# 477ProjectBattery.net
KiCad netlist of a schematic drawn in EAGLE
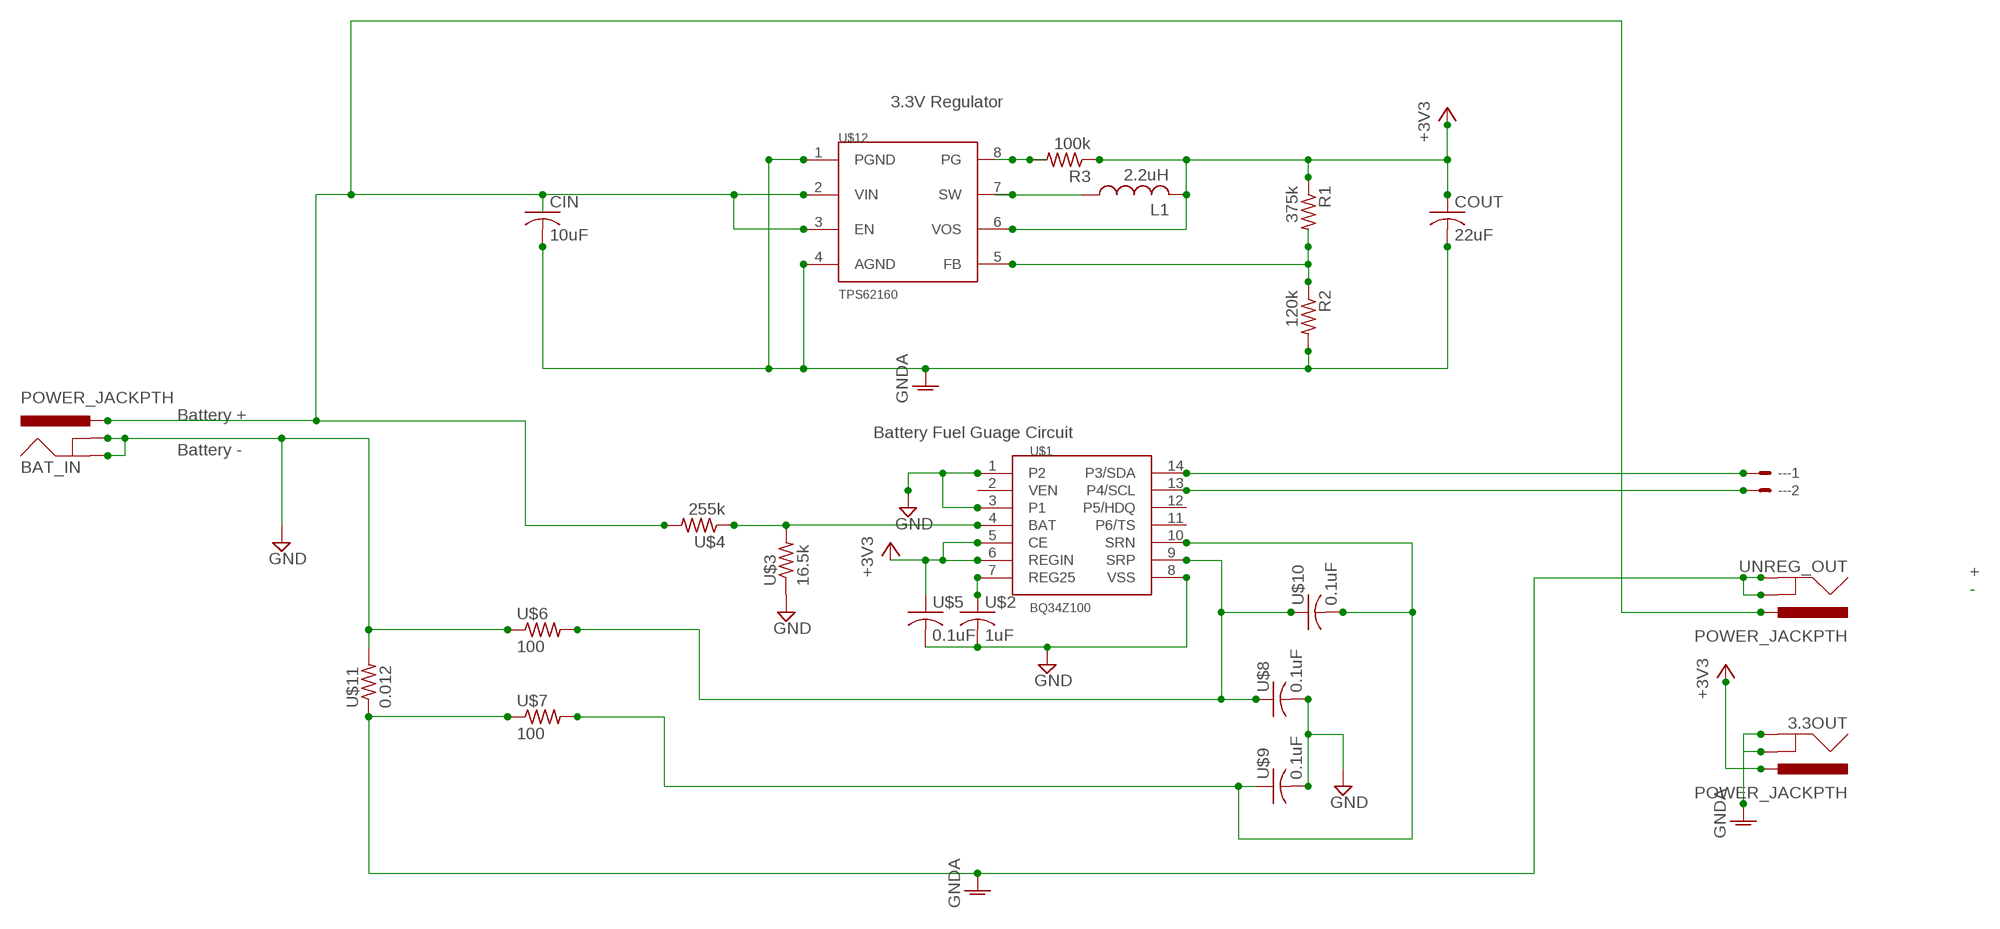
[diagram p0: schematic, sheet 1]

(export (version "E")
  (design (tool "Eeschema 10.0.6"))
  (components
    (comp (ref "--")
      (value "22-23-2021")
      (footprint "eagle-import:22-23-2021")
      (fields (field (name "MF") "MOLEX"))
      (libsource (lib "eagle-import") (part "22-23-2021"))
    )
    (comp (ref "3.3OUT")
      (value "POWER_JACKPTH")
      (footprint "eagle-import:POWER_JACK_PTH")
      (libsource (lib "eagle-import") (part "POWER_JACKPTH"))
    )
    (comp (ref "BAT_IN")
      (value "POWER_JACKPTH")
      (footprint "eagle-import:POWER_JACK_PTH")
      (libsource (lib "eagle-import") (part "POWER_JACKPTH"))
    )
    (comp (ref "CIN")
      (value "10uF")
      (footprint "eagle-import:C1206")
      (libsource (lib "eagle-import") (part "C-US-1206"))
    )
    (comp (ref "COUT")
      (value "22uF")
      (footprint "eagle-import:C1206")
      (libsource (lib "eagle-import") (part "C-US-1206"))
    )
    (comp (ref "L1")
      (value "2.2uH")
      (footprint "eagle-import:SDR0403")
      (libsource (lib "eagle-import") (part "SDR0403"))
    )
    (comp (ref "R1")
      (value "375k")
      (footprint "eagle-import:R1206")
      (libsource (lib "eagle-import") (part "R-US{dblquote}"))
    )
    (comp (ref "R2")
      (value "120k")
      (footprint "eagle-import:R1206")
      (libsource (lib "eagle-import") (part "R-US{dblquote}"))
    )
    (comp (ref "R3")
      (value "100k")
      (footprint "eagle-import:R1206")
      (libsource (lib "eagle-import") (part "R-US{dblquote}"))
    )
    (comp (ref "U$1")
      (value "BQ34Z100")
      (footprint "eagle-import:SSOP-14")
      (libsource (lib "eagle-import") (part "BQ34Z100"))
    )
    (comp (ref "U$2")
      (value "1uF")
      (footprint "eagle-import:C1206")
      (libsource (lib "eagle-import") (part "C-US-1206"))
    )
    (comp (ref "U$3")
      (value "16.5k")
      (footprint "eagle-import:R1206")
      (libsource (lib "eagle-import") (part "R-US{dblquote}"))
    )
    (comp (ref "U$4")
      (value "255k")
      (footprint "eagle-import:R1206")
      (libsource (lib "eagle-import") (part "R-US{dblquote}"))
    )
    (comp (ref "U$5")
      (value "0.1uF")
      (footprint "eagle-import:C1206")
      (libsource (lib "eagle-import") (part "C-US-1206"))
    )
    (comp (ref "U$6")
      (value "100")
      (footprint "eagle-import:R1206")
      (libsource (lib "eagle-import") (part "R-US{dblquote}"))
    )
    (comp (ref "U$7")
      (value "100")
      (footprint "eagle-import:R1206")
      (libsource (lib "eagle-import") (part "R-US{dblquote}"))
    )
    (comp (ref "U$8")
      (value "0.1uF")
      (footprint "eagle-import:C1206")
      (libsource (lib "eagle-import") (part "C-US-1206"))
    )
    (comp (ref "U$9")
      (value "0.1uF")
      (footprint "eagle-import:C1206")
      (libsource (lib "eagle-import") (part "C-US-1206"))
    )
    (comp (ref "U$10")
      (value "0.1uF")
      (footprint "eagle-import:C1206")
      (libsource (lib "eagle-import") (part "C-US-1206"))
    )
    (comp (ref "U$11")
      (value "0.012")
      (footprint "eagle-import:WSL2816")
      (libsource (lib "eagle-import") (part "R-USCS"))
    )
    (comp (ref "U$12")
      (value "TPS62160")
      (footprint "eagle-import:MSOP-8")
      (libsource (lib "eagle-import") (part "TPS62160"))
    )
    (comp (ref "UNREG_OUT")
      (value "POWER_JACKPTH")
      (footprint "eagle-import:POWER_JACK_PTH")
      (libsource (lib "eagle-import") (part "POWER_JACKPTH"))
    )
  )
  (nets
    (net (code "1") (name "+3V3") (class "Default")
      (node (ref "3.3OUT") (pin "PWR") (pinfunction "PWR_PWR") (pintype "bidirectional"))
      (node (ref "COUT") (pin "1") (pinfunction "1_1") (pintype "passive"))
      (node (ref "L1") (pin "B") (pinfunction "2_B") (pintype "passive"))
      (node (ref "R1") (pin "1") (pinfunction "1_1") (pintype "passive"))
      (node (ref "R3") (pin "1") (pinfunction "1_1") (pintype "passive"))
      (node (ref "U$1") (pin "5") (pinfunction "CE_5") (pintype "bidirectional"))
      (node (ref "U$1") (pin "6") (pinfunction "REGIN_6") (pintype "bidirectional"))
      (node (ref "U$12") (pin "6") (pinfunction "VOS_6") (pintype "bidirectional"))
      (node (ref "U$5") (pin "1") (pinfunction "1_1") (pintype "passive"))
    )
    (net (code "2") (name "GND") (class "Default")
      (node (ref "BAT_IN") (pin "GND") (pinfunction "GND_GND") (pintype "bidirectional"))
      (node (ref "BAT_IN") (pin "GNDBREAK") (pinfunction "GNDBREAK_GNDBREAK") (pintype "bidirectional"))
      (node (ref "U$1") (pin "1") (pinfunction "P2_1") (pintype "bidirectional"))
      (node (ref "U$1") (pin "3") (pinfunction "P1_3") (pintype "bidirectional"))
      (node (ref "U$1") (pin "8") (pinfunction "VSS_8") (pintype "bidirectional"))
      (node (ref "U$11") (pin "2") (pinfunction "2_2") (pintype "passive"))
      (node (ref "U$2") (pin "2") (pinfunction "2_2") (pintype "passive"))
      (node (ref "U$3") (pin "1") (pinfunction "1_1") (pintype "passive"))
      (node (ref "U$5") (pin "2") (pinfunction "2_2") (pintype "passive"))
      (node (ref "U$6") (pin "1") (pinfunction "1_1") (pintype "passive"))
      (node (ref "U$8") (pin "2") (pinfunction "2_2") (pintype "passive"))
      (node (ref "U$9") (pin "2") (pinfunction "2_2") (pintype "passive"))
    )
    (net (code "3") (name "GNDA") (class "Default")
      (node (ref "3.3OUT") (pin "GND") (pinfunction "GND_GND") (pintype "bidirectional"))
      (node (ref "3.3OUT") (pin "GNDBREAK") (pinfunction "GNDBREAK_GNDBREAK") (pintype "bidirectional"))
      (node (ref "CIN") (pin "2") (pinfunction "2_2") (pintype "passive"))
      (node (ref "COUT") (pin "2") (pinfunction "2_2") (pintype "passive"))
      (node (ref "R2") (pin "2") (pinfunction "2_2") (pintype "passive"))
      (node (ref "U$11") (pin "1") (pinfunction "1_1") (pintype "passive"))
      (node (ref "U$12") (pin "1") (pinfunction "PGND_1") (pintype "bidirectional"))
      (node (ref "U$12") (pin "4") (pinfunction "AGND_4") (pintype "bidirectional"))
      (node (ref "U$7") (pin "1") (pinfunction "1_1") (pintype "passive"))
      (node (ref "UNREG_OUT") (pin "GND") (pinfunction "GND_GND") (pintype "bidirectional"))
      (node (ref "UNREG_OUT") (pin "GNDBREAK") (pinfunction "GNDBREAK_GNDBREAK") (pintype "bidirectional"))
    )
    (net (code "4") (name "Net-(--A-S)") (class "Default")
      (node (ref "--") (pin "1") (pinfunction "S_1") (pintype "passive"))
      (node (ref "U$1") (pin "14") (pinfunction "P3/SDA_14") (pintype "bidirectional"))
    )
    (net (code "5") (name "Net-(--B-S)") (class "Default")
      (node (ref "--") (pin "2") (pinfunction "S_2") (pintype "passive"))
      (node (ref "U$1") (pin "13") (pinfunction "P4/SCL_13") (pintype "bidirectional"))
    )
    (net (code "6") (name "Net-(L1-1)") (class "Default")
      (node (ref "L1") (pin "A") (pinfunction "1_A") (pintype "passive"))
      (node (ref "U$12") (pin "7") (pinfunction "SW_7") (pintype "bidirectional"))
    )
    (net (code "7") (name "Net-(U$1-BAT)") (class "Default")
      (node (ref "U$1") (pin "4") (pinfunction "BAT_4") (pintype "bidirectional"))
      (node (ref "U$3") (pin "2") (pinfunction "2_2") (pintype "passive"))
      (node (ref "U$4") (pin "1") (pinfunction "1_1") (pintype "passive"))
    )
    (net (code "8") (name "Net-(U$1-REG25)") (class "Default")
      (node (ref "U$1") (pin "7") (pinfunction "REG25_7") (pintype "bidirectional"))
      (node (ref "U$2") (pin "1") (pinfunction "1_1") (pintype "passive"))
    )
    (net (code "9") (name "Net-(U$1-SRN)") (class "Default")
      (node (ref "U$1") (pin "10") (pinfunction "SRN_10") (pintype "bidirectional"))
      (node (ref "U$10") (pin "2") (pinfunction "2_2") (pintype "passive"))
      (node (ref "U$7") (pin "2") (pinfunction "2_2") (pintype "passive"))
      (node (ref "U$9") (pin "1") (pinfunction "1_1") (pintype "passive"))
    )
    (net (code "10") (name "Net-(U$1-SRP)") (class "Default")
      (node (ref "U$1") (pin "9") (pinfunction "SRP_9") (pintype "bidirectional"))
      (node (ref "U$10") (pin "1") (pinfunction "1_1") (pintype "passive"))
      (node (ref "U$6") (pin "2") (pinfunction "2_2") (pintype "passive"))
      (node (ref "U$8") (pin "1") (pinfunction "1_1") (pintype "passive"))
    )
    (net (code "11") (name "Net-(U$12-EN)") (class "Default")
      (node (ref "BAT_IN") (pin "PWR") (pinfunction "PWR_PWR") (pintype "bidirectional"))
      (node (ref "CIN") (pin "1") (pinfunction "1_1") (pintype "passive"))
      (node (ref "U$12") (pin "2") (pinfunction "VIN_2") (pintype "bidirectional"))
      (node (ref "U$12") (pin "3") (pinfunction "EN_3") (pintype "bidirectional"))
      (node (ref "U$4") (pin "2") (pinfunction "2_2") (pintype "passive"))
      (node (ref "UNREG_OUT") (pin "PWR") (pinfunction "PWR_PWR") (pintype "bidirectional"))
    )
    (net (code "12") (name "Net-(U$12-FB)") (class "Default")
      (node (ref "R1") (pin "2") (pinfunction "2_2") (pintype "passive"))
      (node (ref "R2") (pin "1") (pinfunction "1_1") (pintype "passive"))
      (node (ref "U$12") (pin "5") (pinfunction "FB_5") (pintype "bidirectional"))
    )
    (net (code "13") (name "Net-(U$12-PG)") (class "Default")
      (node (ref "R3") (pin "2") (pinfunction "2_2") (pintype "passive"))
      (node (ref "U$12") (pin "8") (pinfunction "PG_8") (pintype "bidirectional"))
    )
    (net (code "14") (name "unconnected-(U$1-P5{slash}HDQ-Pad12)") (class "Default")
      (node (ref "U$1") (pin "12") (pinfunction "P5/HDQ_12") (pintype "bidirectional"))
    )
    (net (code "15") (name "unconnected-(U$1-P6{slash}TS-Pad11)") (class "Default")
      (node (ref "U$1") (pin "11") (pinfunction "P6/TS_11") (pintype "bidirectional"))
    )
    (net (code "16") (name "unconnected-(U$1-VEN-Pad2)") (class "Default")
      (node (ref "U$1") (pin "2") (pinfunction "VEN_2") (pintype "bidirectional"))
    )
  )
)
